# ZYNQ_SOC_ARM.net
KiCad netlist of a schematic drawn in Altium Designer
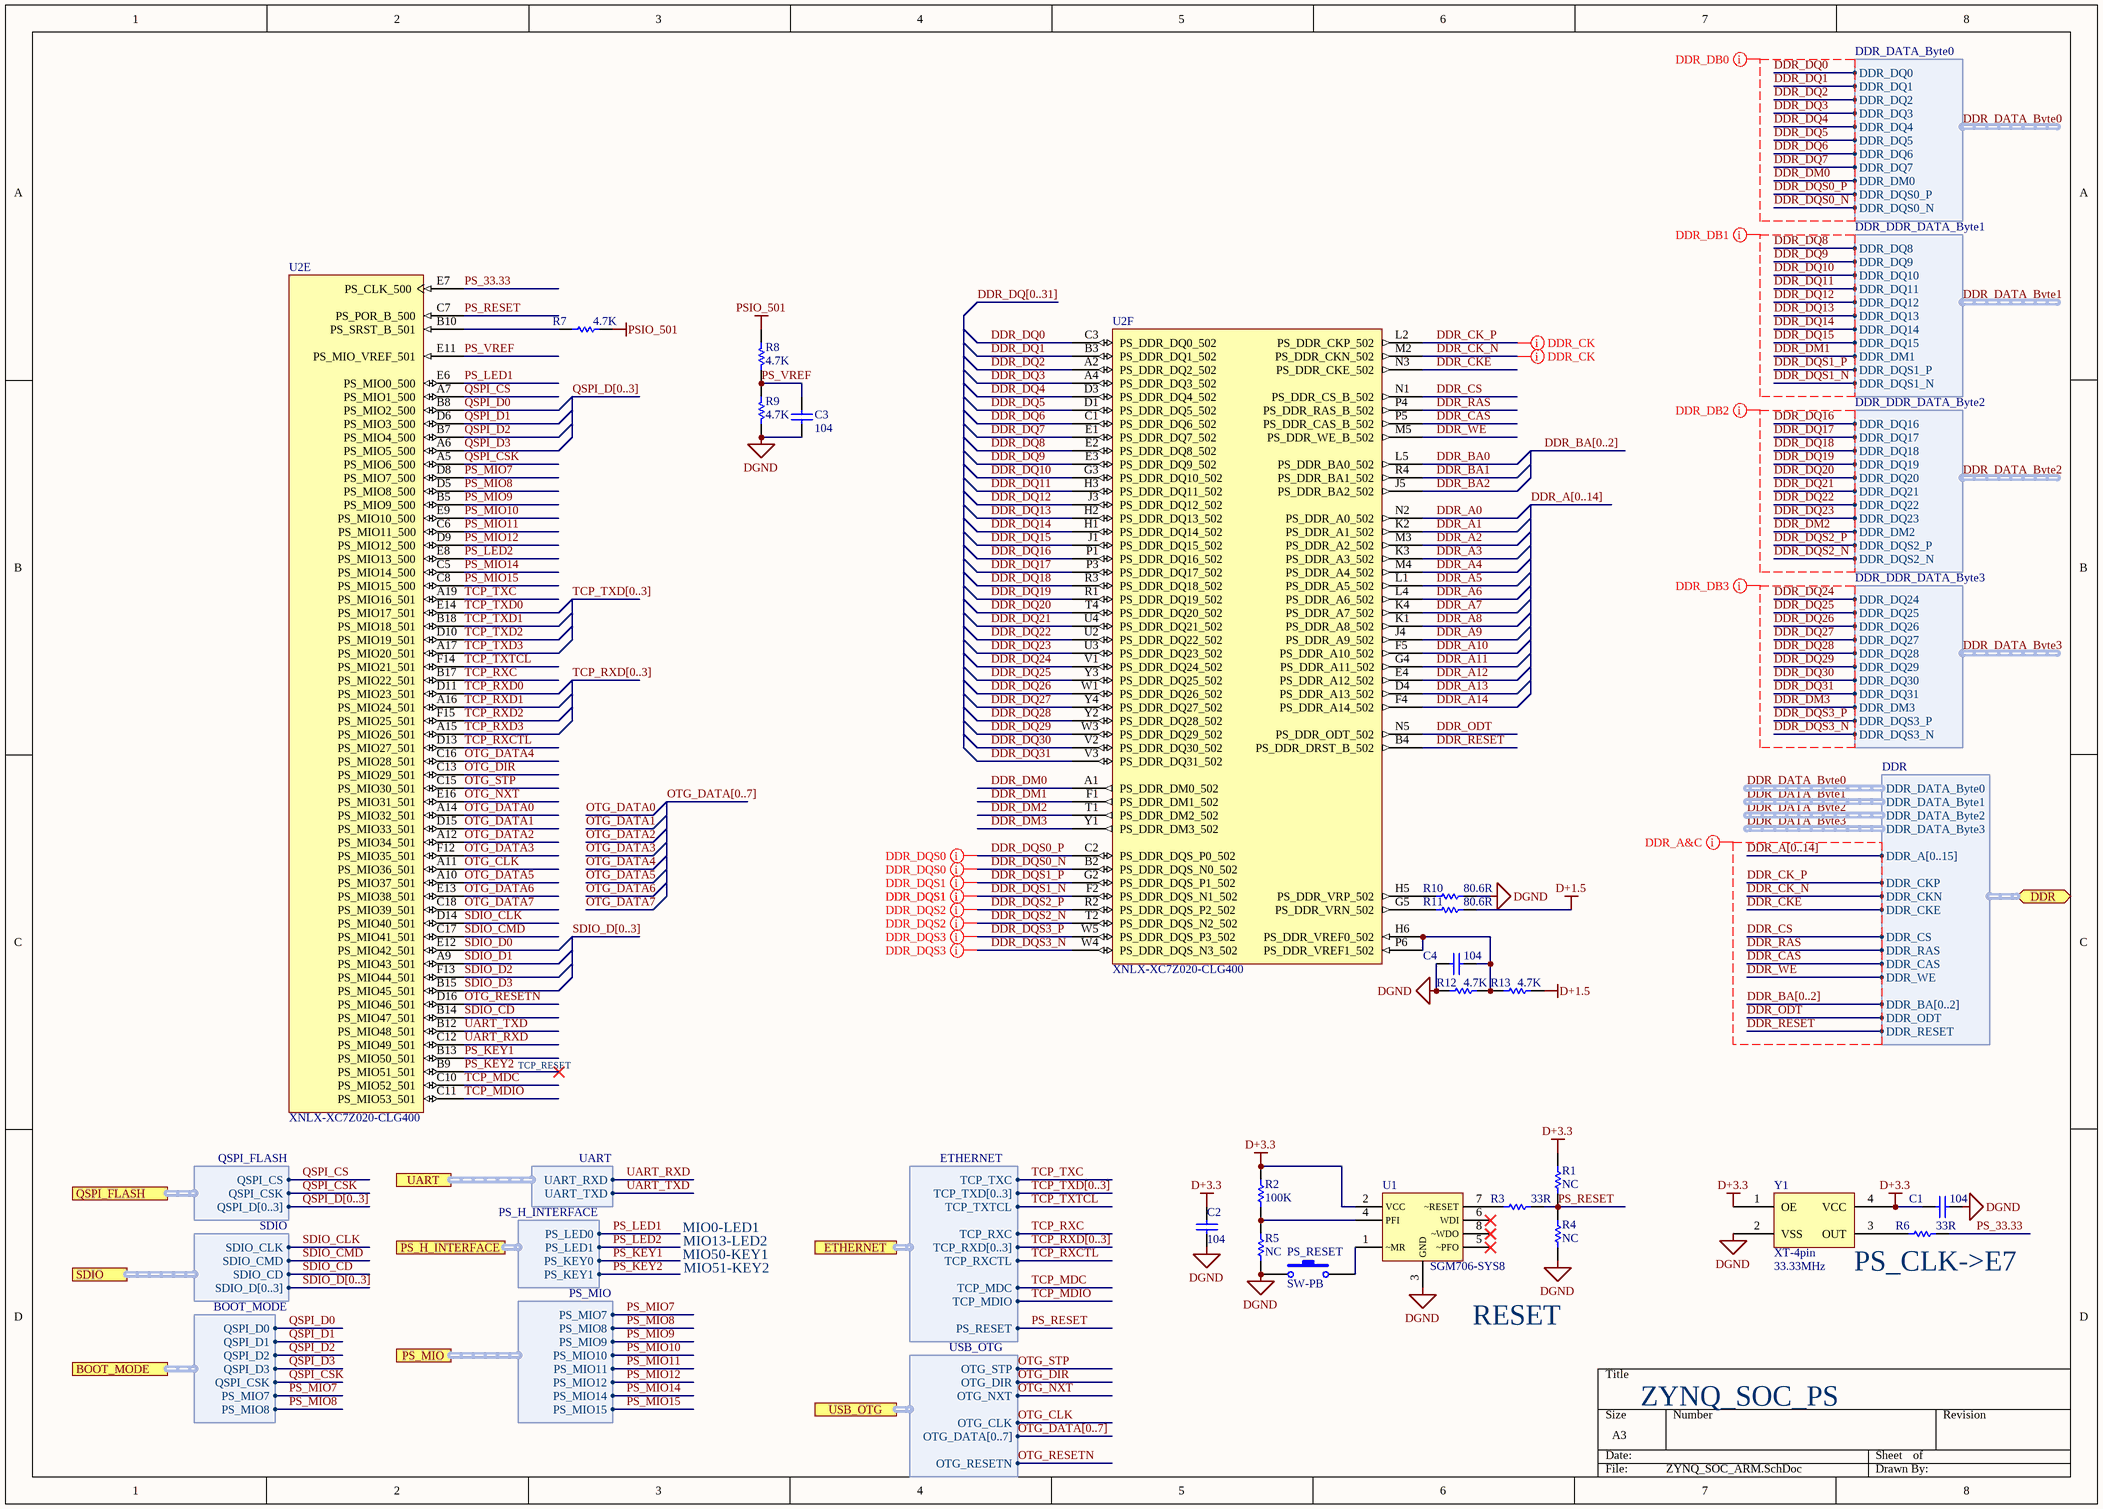
[diagram p0: ZYNQ_SOC_ARM.SchDoc]

(export (version "E")
  (design (tool "Eeschema 10.0.6"))
  (components
    (comp (ref "C1")
      (value "104")
      (footprint "C 0402_LL")
      (description "Capacitor")
      (fields (field (name "PUBLISHER") "Altium Limited"))
      (libsource (lib "Miscellaneous Devices") (part "Cap"))
    )
    (comp (ref "C2")
      (value "104")
      (footprint "C 0402_LL")
      (description "Capacitor")
      (fields (field (name "PUBLISHER") "Altium Limited"))
      (libsource (lib "Miscellaneous Devices") (part "Cap"))
    )
    (comp (ref "C3")
      (value "104")
      (footprint "C 0402_LL")
      (description "Capacitor")
      (fields (field (name "PUBLISHER") "Altium Limited"))
      (libsource (lib "Miscellaneous Devices") (part "Cap"))
    )
    (comp (ref "C4")
      (value "104")
      (footprint "C 0402_LL")
      (description "Capacitor")
      (fields (field (name "PUBLISHER") "Altium Limited"))
      (libsource (lib "Miscellaneous Devices") (part "Cap"))
    )
    (comp (ref "PS_RESET")
      (value "SW-PB")
      (footprint "TSW SMD-3*6*4.3")
      (description "Switch")
      (fields (field (name "PUBLISHER") "Altium Limited"))
      (libsource (lib "Miscellaneous Devices") (part "SW-PB"))
    )
    (comp (ref "R1")
      (value "NC")
      (footprint "R 0402_L")
      (description "Resistor")
      (fields (field (name "PUBLISHER") "Altium Limited"))
      (libsource (lib "Miscellaneous Devices") (part "Res1"))
    )
    (comp (ref "R2")
      (value "100K")
      (footprint "R 0603_L")
      (description "Resistor")
      (fields (field (name "PUBLISHER") "Altium Limited"))
      (libsource (lib "Miscellaneous Devices") (part "Res1"))
    )
    (comp (ref "R3")
      (value "33R")
      (footprint "R 0603_L")
      (description "Resistor")
      (fields (field (name "PUBLISHER") "Altium Limited"))
      (libsource (lib "Miscellaneous Devices") (part "Res1"))
    )
    (comp (ref "R4")
      (value "NC")
      (footprint "R 0402_L")
      (description "Resistor")
      (fields (field (name "PUBLISHER") "Altium Limited"))
      (libsource (lib "Miscellaneous Devices") (part "Res1"))
    )
    (comp (ref "R5")
      (value "NC")
      (footprint "R 0402_L")
      (description "Resistor")
      (fields (field (name "PUBLISHER") "Altium Limited"))
      (libsource (lib "Miscellaneous Devices") (part "Res1"))
    )
    (comp (ref "R6")
      (value "33R")
      (footprint "R 0603_L")
      (description "Resistor")
      (fields (field (name "PUBLISHER") "Altium Limited"))
      (libsource (lib "Miscellaneous Devices") (part "Res1"))
    )
    (comp (ref "R7")
      (value "4.7K")
      (footprint "R 0402_L")
      (description "Resistor")
      (fields (field (name "PUBLISHER") "Altium Limited"))
      (libsource (lib "Miscellaneous Devices") (part "Res1"))
    )
    (comp (ref "R8")
      (value "4.7K")
      (footprint "R 0402_L")
      (description "Resistor")
      (fields (field (name "PUBLISHER") "Altium Limited"))
      (libsource (lib "Miscellaneous Devices") (part "Res1"))
    )
    (comp (ref "R9")
      (value "4.7K")
      (footprint "R 0402_L")
      (description "Resistor")
      (fields (field (name "PUBLISHER") "Altium Limited"))
      (libsource (lib "Miscellaneous Devices") (part "Res1"))
    )
    (comp (ref "R10")
      (value "80.6R")
      (footprint "R 0402_L")
      (description "Resistor")
      (fields (field (name "PUBLISHER") "Altium Limited"))
      (libsource (lib "Miscellaneous Devices") (part "Res1"))
    )
    (comp (ref "R11")
      (value "80.6R")
      (footprint "R 0402_L")
      (description "Resistor")
      (fields (field (name "PUBLISHER") "Altium Limited"))
      (libsource (lib "Miscellaneous Devices") (part "Res1"))
    )
    (comp (ref "R12")
      (value "4.7K")
      (footprint "R 0402_L")
      (description "Resistor")
      (fields (field (name "PUBLISHER") "Altium Limited"))
      (libsource (lib "Miscellaneous Devices") (part "Res1"))
    )
    (comp (ref "R13")
      (value "4.7K")
      (footprint "R 0402_L")
      (description "Resistor")
      (fields (field (name "PUBLISHER") "Altium Limited"))
      (libsource (lib "Miscellaneous Devices") (part "Res1"))
    )
    (comp (ref "U1")
      (value "SGM706-SYS8")
      (footprint "SOP8_N")
      (description "power supply monitoring circuitry for power on time.")
      (libsource (lib "ZYNQ7010_add") (part "SGM706"))
    )
    (comp (ref "U2")
      (value "XNLX-XC7Z020-CLG400")
      (footprint "BGA400")
      (description "xilinx双核A9处理器与FPGA集成的SoC")
      (fields (field (name "MANUFACTURER") "xilinx"))
      (libsource (lib "龙井V1") (part "XNLX-XC7Z020-CLG400"))
    )
    (comp (ref "Y1")
      (value "XT-4pin")
      (footprint "5032(P)")
      (description "有源晶振")
      (fields (field (name "MANUFACTURER") "NC") (field (name "ALTIUM_VALUE") "33.33MHz"))
      (libsource (lib "龙井V1") (part "XT-4pin"))
    )
  )
  (nets
    (net (code "18") (name "/DDR_A0") (class "Default")
      (node (ref "U2") (pin "N2") (pinfunction "PS_DDR_A0_502_N2") (pintype "output"))
    )
    (net (code "19") (name "/DDR_A1") (class "Default")
      (node (ref "U2") (pin "K2") (pinfunction "PS_DDR_A1_502_K2") (pintype "output"))
    )
    (net (code "20") (name "/DDR_A2") (class "Default")
      (node (ref "U2") (pin "M3") (pinfunction "PS_DDR_A2_502_M3") (pintype "output"))
    )
    (net (code "21") (name "/DDR_A3") (class "Default")
      (node (ref "U2") (pin "K3") (pinfunction "PS_DDR_A3_502_K3") (pintype "output"))
    )
    (net (code "22") (name "/DDR_A4") (class "Default")
      (node (ref "U2") (pin "M4") (pinfunction "PS_DDR_A4_502_M4") (pintype "output"))
    )
    (net (code "23") (name "/DDR_A5") (class "Default")
      (node (ref "U2") (pin "L1") (pinfunction "PS_DDR_A5_502_L1") (pintype "output"))
    )
    (net (code "24") (name "/DDR_A6") (class "Default")
      (node (ref "U2") (pin "L4") (pinfunction "PS_DDR_A6_502_L4") (pintype "output"))
    )
    (net (code "25") (name "/DDR_A7") (class "Default")
      (node (ref "U2") (pin "K4") (pinfunction "PS_DDR_A7_502_K4") (pintype "output"))
    )
    (net (code "26") (name "/DDR_A8") (class "Default")
      (node (ref "U2") (pin "K1") (pinfunction "PS_DDR_A8_502_K1") (pintype "output"))
    )
    (net (code "27") (name "/DDR_A9") (class "Default")
      (node (ref "U2") (pin "J4") (pinfunction "PS_DDR_A9_502_J4") (pintype "output"))
    )
    (net (code "28") (name "/DDR_A10") (class "Default")
      (node (ref "U2") (pin "F5") (pinfunction "PS_DDR_A10_502_F5") (pintype "output"))
    )
    (net (code "29") (name "/DDR_A11") (class "Default")
      (node (ref "U2") (pin "G4") (pinfunction "PS_DDR_A11_502_G4") (pintype "output"))
    )
    (net (code "30") (name "/DDR_A12") (class "Default")
      (node (ref "U2") (pin "E4") (pinfunction "PS_DDR_A12_502_E4") (pintype "output"))
    )
    (net (code "31") (name "/DDR_A13") (class "Default")
      (node (ref "U2") (pin "D4") (pinfunction "PS_DDR_A13_502_D4") (pintype "output"))
    )
    (net (code "32") (name "/DDR_A14") (class "Default")
      (node (ref "U2") (pin "F4") (pinfunction "PS_DDR_A14_502_F4") (pintype "output"))
    )
    (net (code "34") (name "/DDR_BA0") (class "Default")
      (node (ref "U2") (pin "L5") (pinfunction "PS_DDR_BA0_502_L5") (pintype "output"))
    )
    (net (code "35") (name "/DDR_BA1") (class "Default")
      (node (ref "U2") (pin "R4") (pinfunction "PS_DDR_BA1_502_R4") (pintype "output"))
    )
    (net (code "36") (name "/DDR_BA2") (class "Default")
      (node (ref "U2") (pin "J5") (pinfunction "PS_DDR_BA2_502_J5") (pintype "output"))
    )
    (net (code "38") (name "/DDR_CAS") (class "Default")
      (node (ref "U2") (pin "P5") (pinfunction "PS_DDR_CAS_B_502_P5") (pintype "output"))
    )
    (net (code "39") (name "/DDR_CKE") (class "Default")
      (node (ref "U2") (pin "N3") (pinfunction "PS_DDR_CKE_502_N3") (pintype "output"))
    )
    (net (code "40") (name "/DDR_CK_N") (class "Default")
      (node (ref "U2") (pin "M2") (pinfunction "PS_DDR_CKN_502_M2") (pintype "output"))
    )
    (net (code "41") (name "/DDR_CK_P") (class "Default")
      (node (ref "U2") (pin "L2") (pinfunction "PS_DDR_CKP_502_L2") (pintype "output"))
    )
    (net (code "42") (name "/DDR_CS") (class "Default")
      (node (ref "U2") (pin "N1") (pinfunction "PS_DDR_CS_B_502_N1") (pintype "output"))
    )
    (net (code "47") (name "/DDR_DM0") (class "Default")
      (node (ref "U2") (pin "A1") (pinfunction "PS_DDR_DM0_502_A1") (pintype "output"))
    )
    (net (code "48") (name "/DDR_DM1") (class "Default")
      (node (ref "U2") (pin "F1") (pinfunction "PS_DDR_DM1_502_F1") (pintype "output"))
    )
    (net (code "49") (name "/DDR_DM2") (class "Default")
      (node (ref "U2") (pin "T1") (pinfunction "PS_DDR_DM2_502_T1") (pintype "output"))
    )
    (net (code "50") (name "/DDR_DM3") (class "Default")
      (node (ref "U2") (pin "Y1") (pinfunction "PS_DDR_DM3_502_Y1") (pintype "output"))
    )
    (net (code "51") (name "/DDR_DQ0") (class "Default")
      (node (ref "U2") (pin "C3") (pinfunction "PS_DDR_DQ0_502_C3") (pintype "bidirectional"))
    )
    (net (code "52") (name "/DDR_DQ1") (class "Default")
      (node (ref "U2") (pin "B3") (pinfunction "PS_DDR_DQ1_502_B3") (pintype "bidirectional"))
    )
    (net (code "53") (name "/DDR_DQ2") (class "Default")
      (node (ref "U2") (pin "A2") (pinfunction "PS_DDR_DQ2_502_A2") (pintype "bidirectional"))
    )
    (net (code "54") (name "/DDR_DQ3") (class "Default")
      (node (ref "U2") (pin "A4") (pinfunction "PS_DDR_DQ3_502_A4") (pintype "bidirectional"))
    )
    (net (code "55") (name "/DDR_DQ4") (class "Default")
      (node (ref "U2") (pin "D3") (pinfunction "PS_DDR_DQ4_502_D3") (pintype "bidirectional"))
    )
    (net (code "56") (name "/DDR_DQ5") (class "Default")
      (node (ref "U2") (pin "D1") (pinfunction "PS_DDR_DQ5_502_D1") (pintype "bidirectional"))
    )
    (net (code "57") (name "/DDR_DQ6") (class "Default")
      (node (ref "U2") (pin "C1") (pinfunction "PS_DDR_DQ6_502_C1") (pintype "bidirectional"))
    )
    (net (code "58") (name "/DDR_DQ7") (class "Default")
      (node (ref "U2") (pin "E1") (pinfunction "PS_DDR_DQ7_502_E1") (pintype "bidirectional"))
    )
    (net (code "59") (name "/DDR_DQ8") (class "Default")
      (node (ref "U2") (pin "E2") (pinfunction "PS_DDR_DQ8_502_E2") (pintype "bidirectional"))
    )
    (net (code "60") (name "/DDR_DQ9") (class "Default")
      (node (ref "U2") (pin "E3") (pinfunction "PS_DDR_DQ9_502_E3") (pintype "bidirectional"))
    )
    (net (code "61") (name "/DDR_DQ10") (class "Default")
      (node (ref "U2") (pin "G3") (pinfunction "PS_DDR_DQ10_502_G3") (pintype "bidirectional"))
    )
    (net (code "62") (name "/DDR_DQ11") (class "Default")
      (node (ref "U2") (pin "H3") (pinfunction "PS_DDR_DQ11_502_H3") (pintype "bidirectional"))
    )
    (net (code "63") (name "/DDR_DQ12") (class "Default")
      (node (ref "U2") (pin "J3") (pinfunction "PS_DDR_DQ12_502_J3") (pintype "bidirectional"))
    )
    (net (code "64") (name "/DDR_DQ13") (class "Default")
      (node (ref "U2") (pin "H2") (pinfunction "PS_DDR_DQ13_502_H2") (pintype "bidirectional"))
    )
    (net (code "65") (name "/DDR_DQ14") (class "Default")
      (node (ref "U2") (pin "H1") (pinfunction "PS_DDR_DQ14_502_H1") (pintype "bidirectional"))
    )
    (net (code "66") (name "/DDR_DQ15") (class "Default")
      (node (ref "U2") (pin "J1") (pinfunction "PS_DDR_DQ15_502_J1") (pintype "bidirectional"))
    )
    (net (code "67") (name "/DDR_DQ16") (class "Default")
      (node (ref "U2") (pin "P1") (pinfunction "PS_DDR_DQ16_502_P1") (pintype "bidirectional"))
    )
    (net (code "68") (name "/DDR_DQ17") (class "Default")
      (node (ref "U2") (pin "P3") (pinfunction "PS_DDR_DQ17_502_P3") (pintype "bidirectional"))
    )
    (net (code "69") (name "/DDR_DQ18") (class "Default")
      (node (ref "U2") (pin "R3") (pinfunction "PS_DDR_DQ18_502_R3") (pintype "bidirectional"))
    )
    (net (code "70") (name "/DDR_DQ19") (class "Default")
      (node (ref "U2") (pin "R1") (pinfunction "PS_DDR_DQ19_502_R1") (pintype "bidirectional"))
    )
    (net (code "71") (name "/DDR_DQ20") (class "Default")
      (node (ref "U2") (pin "T4") (pinfunction "PS_DDR_DQ20_502_T4") (pintype "bidirectional"))
    )
    (net (code "72") (name "/DDR_DQ21") (class "Default")
      (node (ref "U2") (pin "U4") (pinfunction "PS_DDR_DQ21_502_U4") (pintype "bidirectional"))
    )
    (net (code "73") (name "/DDR_DQ22") (class "Default")
      (node (ref "U2") (pin "U2") (pinfunction "PS_DDR_DQ22_502_U2") (pintype "bidirectional"))
    )
    (net (code "74") (name "/DDR_DQ23") (class "Default")
      (node (ref "U2") (pin "U3") (pinfunction "PS_DDR_DQ23_502_U3") (pintype "bidirectional"))
    )
    (net (code "75") (name "/DDR_DQ24") (class "Default")
      (node (ref "U2") (pin "V1") (pinfunction "PS_DDR_DQ24_502_V1") (pintype "bidirectional"))
    )
    (net (code "76") (name "/DDR_DQ25") (class "Default")
      (node (ref "U2") (pin "Y3") (pinfunction "PS_DDR_DQ25_502_Y3") (pintype "bidirectional"))
    )
    (net (code "77") (name "/DDR_DQ26") (class "Default")
      (node (ref "U2") (pin "W1") (pinfunction "PS_DDR_DQ26_502_W1") (pintype "bidirectional"))
    )
    (net (code "78") (name "/DDR_DQ27") (class "Default")
      (node (ref "U2") (pin "Y4") (pinfunction "PS_DDR_DQ27_502_Y4") (pintype "bidirectional"))
    )
    (net (code "79") (name "/DDR_DQ28") (class "Default")
      (node (ref "U2") (pin "Y2") (pinfunction "PS_DDR_DQ28_502_Y2") (pintype "bidirectional"))
    )
    (net (code "80") (name "/DDR_DQ29") (class "Default")
      (node (ref "U2") (pin "W3") (pinfunction "PS_DDR_DQ29_502_W3") (pintype "bidirectional"))
    )
    (net (code "81") (name "/DDR_DQ30") (class "Default")
      (node (ref "U2") (pin "V2") (pinfunction "PS_DDR_DQ30_502_V2") (pintype "bidirectional"))
    )
    (net (code "82") (name "/DDR_DQ31") (class "Default")
      (node (ref "U2") (pin "V3") (pinfunction "PS_DDR_DQ31_502_V3") (pintype "bidirectional"))
    )
    (net (code "83") (name "/DDR_DQS0_N") (class "Default")
      (node (ref "U2") (pin "B2") (pinfunction "PS_DDR_DQS_N0_502_B2") (pintype "bidirectional"))
    )
    (net (code "84") (name "/DDR_DQS0_P") (class "Default")
      (node (ref "U2") (pin "C2") (pinfunction "PS_DDR_DQS_P0_502_C2") (pintype "bidirectional"))
    )
    (net (code "85") (name "/DDR_DQS1_N") (class "Default")
      (node (ref "U2") (pin "F2") (pinfunction "PS_DDR_DQS_N1_502_F2") (pintype "bidirectional"))
    )
    (net (code "86") (name "/DDR_DQS1_P") (class "Default")
      (node (ref "U2") (pin "G2") (pinfunction "PS_DDR_DQS_P1_502_G2") (pintype "bidirectional"))
    )
    (net (code "87") (name "/DDR_DQS2_N") (class "Default")
      (node (ref "U2") (pin "T2") (pinfunction "PS_DDR_DQS_N2_502_T2") (pintype "bidirectional"))
    )
    (net (code "88") (name "/DDR_DQS2_P") (class "Default")
      (node (ref "U2") (pin "R2") (pinfunction "PS_DDR_DQS_P2_502_R2") (pintype "bidirectional"))
    )
    (net (code "89") (name "/DDR_DQS3_N") (class "Default")
      (node (ref "U2") (pin "W4") (pinfunction "PS_DDR_DQS_N3_502_W4") (pintype "bidirectional"))
    )
    (net (code "90") (name "/DDR_DQS3_P") (class "Default")
      (node (ref "U2") (pin "W5") (pinfunction "PS_DDR_DQS_P3_502_W5") (pintype "bidirectional"))
    )
    (net (code "92") (name "/DDR_ODT") (class "Default")
      (node (ref "U2") (pin "N5") (pinfunction "PS_DDR_ODT_502_N5") (pintype "output"))
    )
    (net (code "93") (name "/DDR_RAS") (class "Default")
      (node (ref "U2") (pin "P4") (pinfunction "PS_DDR_RAS_B_502_P4") (pintype "output"))
    )
    (net (code "94") (name "/DDR_RESET") (class "Default")
      (node (ref "U2") (pin "B4") (pinfunction "PS_DDR_DRST_B_502_B4") (pintype "output"))
    )
    (net (code "95") (name "/DDR_WE") (class "Default")
      (node (ref "U2") (pin "M5") (pinfunction "PS_DDR_WE_B_502_M5") (pintype "output"))
    )
    (net (code "97") (name "/OTG_CLK") (class "Default")
      (node (ref "U2") (pin "A11") (pinfunction "PS_MIO36_501_A11") (pintype "bidirectional"))
    )
    (net (code "98") (name "/OTG_DATA0") (class "Default")
      (node (ref "U2") (pin "A14") (pinfunction "PS_MIO32_501_A14") (pintype "bidirectional"))
    )
    (net (code "99") (name "/OTG_DATA1") (class "Default")
      (node (ref "U2") (pin "D15") (pinfunction "PS_MIO33_501_D15") (pintype "bidirectional"))
    )
    (net (code "100") (name "/OTG_DATA2") (class "Default")
      (node (ref "U2") (pin "A12") (pinfunction "PS_MIO34_501_A12") (pintype "bidirectional"))
    )
    (net (code "101") (name "/OTG_DATA3") (class "Default")
      (node (ref "U2") (pin "F12") (pinfunction "PS_MIO35_501_F12") (pintype "bidirectional"))
    )
    (net (code "102") (name "/OTG_DATA4") (class "Default")
      (node (ref "U2") (pin "C16") (pinfunction "PS_MIO28_501_C16") (pintype "bidirectional"))
    )
    (net (code "103") (name "/OTG_DATA5") (class "Default")
      (node (ref "U2") (pin "A10") (pinfunction "PS_MIO37_501_A10") (pintype "bidirectional"))
    )
    (net (code "104") (name "/OTG_DATA6") (class "Default")
      (node (ref "U2") (pin "E13") (pinfunction "PS_MIO38_501_E13") (pintype "bidirectional"))
    )
    (net (code "105") (name "/OTG_DATA7") (class "Default")
      (node (ref "U2") (pin "C18") (pinfunction "PS_MIO39_501_C18") (pintype "bidirectional"))
    )
    (net (code "107") (name "/OTG_DIR") (class "Default")
      (node (ref "U2") (pin "C13") (pinfunction "PS_MIO29_501_C13") (pintype "bidirectional"))
    )
    (net (code "108") (name "/OTG_NXT") (class "Default")
      (node (ref "U2") (pin "E16") (pinfunction "PS_MIO31_501_E16") (pintype "bidirectional"))
    )
    (net (code "109") (name "/OTG_RESETN") (class "Default")
      (node (ref "U2") (pin "D16") (pinfunction "PS_MIO46_501_D16") (pintype "bidirectional"))
    )
    (net (code "110") (name "/OTG_STP") (class "Default")
      (node (ref "U2") (pin "C15") (pinfunction "PS_MIO30_501_C15") (pintype "bidirectional"))
    )
    (net (code "111") (name "/PS_33.33") (class "Default")
      (node (ref "R6") (pin "2") (pinfunction "2_2") (pintype "passive"))
      (node (ref "U2") (pin "E7") (pinfunction "PS_CLK_500_E7") (pintype "input"))
    )
    (net (code "112") (name "/PS_KEY1") (class "Default")
      (node (ref "U2") (pin "B13") (pinfunction "PS_MIO50_501_B13") (pintype "bidirectional"))
    )
    (net (code "113") (name "/PS_KEY2") (class "Default")
      (node (ref "U2") (pin "B9") (pinfunction "PS_MIO51_501_B9") (pintype "bidirectional+no_connect"))
    )
    (net (code "114") (name "/PS_LED1") (class "Default")
      (node (ref "U2") (pin "E6") (pinfunction "PS_MIO0_500_E6") (pintype "bidirectional"))
    )
    (net (code "115") (name "/PS_LED2") (class "Default")
      (node (ref "U2") (pin "E8") (pinfunction "PS_MIO13_500_E8") (pintype "bidirectional"))
    )
    (net (code "116") (name "/PS_MIO7") (class "Default")
      (node (ref "U2") (pin "D8") (pinfunction "PS_MIO7_500_D8") (pintype "bidirectional"))
    )
    (net (code "117") (name "/PS_MIO8") (class "Default")
      (node (ref "U2") (pin "D5") (pinfunction "PS_MIO8_500_D5") (pintype "bidirectional"))
    )
    (net (code "118") (name "/PS_MIO9") (class "Default")
      (node (ref "U2") (pin "B5") (pinfunction "PS_MIO9_500_B5") (pintype "bidirectional"))
    )
    (net (code "119") (name "/PS_MIO10") (class "Default")
      (node (ref "U2") (pin "E9") (pinfunction "PS_MIO10_500_E9") (pintype "bidirectional"))
    )
    (net (code "120") (name "/PS_MIO11") (class "Default")
      (node (ref "U2") (pin "C6") (pinfunction "PS_MIO11_500_C6") (pintype "bidirectional"))
    )
    (net (code "121") (name "/PS_MIO12") (class "Default")
      (node (ref "U2") (pin "D9") (pinfunction "PS_MIO12_500_D9") (pintype "bidirectional"))
    )
    (net (code "122") (name "/PS_MIO14") (class "Default")
      (node (ref "U2") (pin "C5") (pinfunction "PS_MIO14_500_C5") (pintype "bidirectional"))
    )
    (net (code "123") (name "/PS_MIO15") (class "Default")
      (node (ref "U2") (pin "C8") (pinfunction "PS_MIO15_500_C8") (pintype "bidirectional"))
    )
    (net (code "124") (name "/PS_RESET") (class "Default")
      (node (ref "R1") (pin "1") (pinfunction "1_1") (pintype "passive"))
      (node (ref "R3") (pin "2") (pinfunction "2_2") (pintype "passive"))
      (node (ref "R4") (pin "2") (pinfunction "2_2") (pintype "passive"))
      (node (ref "U2") (pin "C7") (pinfunction "PS_POR_B_500_C7") (pintype "input"))
    )
    (net (code "125") (name "/PS_VREF") (class "Default")
      (node (ref "C3") (pin "2") (pinfunction "2_2") (pintype "passive"))
      (node (ref "R8") (pin "1") (pinfunction "1_1") (pintype "passive"))
      (node (ref "R9") (pin "2") (pinfunction "2_2") (pintype "passive"))
      (node (ref "U2") (pin "E11") (pinfunction "PS_MIO_VREF_501_E11") (pintype "input"))
    )
    (net (code "126") (name "/QSPI_CS") (class "Default")
      (node (ref "U2") (pin "A7") (pinfunction "PS_MIO1_500_A7") (pintype "bidirectional"))
    )
    (net (code "127") (name "/QSPI_CSK") (class "Default")
      (node (ref "U2") (pin "A5") (pinfunction "PS_MIO6_500_A5") (pintype "bidirectional"))
    )
    (net (code "128") (name "/QSPI_D0") (class "Default")
      (node (ref "U2") (pin "B8") (pinfunction "PS_MIO2_500_B8") (pintype "bidirectional"))
    )
    (net (code "129") (name "/QSPI_D1") (class "Default")
      (node (ref "U2") (pin "D6") (pinfunction "PS_MIO3_500_D6") (pintype "bidirectional"))
    )
    (net (code "130") (name "/QSPI_D2") (class "Default")
      (node (ref "U2") (pin "B7") (pinfunction "PS_MIO4_500_B7") (pintype "bidirectional"))
    )
    (net (code "131") (name "/QSPI_D3") (class "Default")
      (node (ref "U2") (pin "A6") (pinfunction "PS_MIO5_500_A6") (pintype "bidirectional"))
    )
    (net (code "133") (name "/SDIO_CD") (class "Default")
      (node (ref "U2") (pin "B14") (pinfunction "PS_MIO47_501_B14") (pintype "bidirectional"))
    )
    (net (code "134") (name "/SDIO_CLK") (class "Default")
      (node (ref "U2") (pin "D14") (pinfunction "PS_MIO40_501_D14") (pintype "bidirectional"))
    )
    (net (code "135") (name "/SDIO_CMD") (class "Default")
      (node (ref "U2") (pin "C17") (pinfunction "PS_MIO41_501_C17") (pintype "bidirectional"))
    )
    (net (code "136") (name "/SDIO_D0") (class "Default")
      (node (ref "U2") (pin "E12") (pinfunction "PS_MIO42_501_E12") (pintype "bidirectional"))
    )
    (net (code "137") (name "/SDIO_D1") (class "Default")
      (node (ref "U2") (pin "A9") (pinfunction "PS_MIO43_501_A9") (pintype "bidirectional"))
    )
    (net (code "138") (name "/SDIO_D2") (class "Default")
      (node (ref "U2") (pin "F13") (pinfunction "PS_MIO44_501_F13") (pintype "bidirectional"))
    )
    (net (code "139") (name "/SDIO_D3") (class "Default")
      (node (ref "U2") (pin "B15") (pinfunction "PS_MIO45_501_B15") (pintype "bidirectional"))
    )
    (net (code "142") (name "/TCP_MDC") (class "Default")
      (node (ref "U2") (pin "C10") (pinfunction "PS_MIO52_501_C10") (pintype "bidirectional"))
    )
    (net (code "143") (name "/TCP_MDIO") (class "Default")
      (node (ref "U2") (pin "C11") (pinfunction "PS_MIO53_501_C11") (pintype "bidirectional"))
    )
    (net (code "144") (name "/TCP_RXC") (class "Default")
      (node (ref "U2") (pin "B17") (pinfunction "PS_MIO22_501_B17") (pintype "bidirectional"))
    )
    (net (code "145") (name "/TCP_RXCTL") (class "Default")
      (node (ref "U2") (pin "D13") (pinfunction "PS_MIO27_501_D13") (pintype "bidirectional"))
    )
    (net (code "146") (name "/TCP_RXD0") (class "Default")
      (node (ref "U2") (pin "D11") (pinfunction "PS_MIO23_501_D11") (pintype "bidirectional"))
    )
    (net (code "147") (name "/TCP_RXD1") (class "Default")
      (node (ref "U2") (pin "A16") (pinfunction "PS_MIO24_501_A16") (pintype "bidirectional"))
    )
    (net (code "148") (name "/TCP_RXD2") (class "Default")
      (node (ref "U2") (pin "F15") (pinfunction "PS_MIO25_501_F15") (pintype "bidirectional"))
    )
    (net (code "149") (name "/TCP_RXD3") (class "Default")
      (node (ref "U2") (pin "A15") (pinfunction "PS_MIO26_501_A15") (pintype "bidirectional"))
    )
    (net (code "151") (name "/TCP_TXC") (class "Default")
      (node (ref "U2") (pin "A19") (pinfunction "PS_MIO16_501_A19") (pintype "bidirectional"))
    )
    (net (code "152") (name "/TCP_TXD0") (class "Default")
      (node (ref "U2") (pin "E14") (pinfunction "PS_MIO17_501_E14") (pintype "bidirectional"))
    )
    (net (code "153") (name "/TCP_TXD1") (class "Default")
      (node (ref "U2") (pin "B18") (pinfunction "PS_MIO18_501_B18") (pintype "bidirectional"))
    )
    (net (code "154") (name "/TCP_TXD2") (class "Default")
      (node (ref "U2") (pin "D10") (pinfunction "PS_MIO19_501_D10") (pintype "bidirectional"))
    )
    (net (code "155") (name "/TCP_TXD3") (class "Default")
      (node (ref "U2") (pin "A17") (pinfunction "PS_MIO20_501_A17") (pintype "bidirectional"))
    )
    (net (code "157") (name "/TCP_TXTCL") (class "Default")
      (node (ref "U2") (pin "F14") (pinfunction "PS_MIO21_501_F14") (pintype "bidirectional"))
    )
    (net (code "158") (name "/UART_RXD") (class "Default")
      (node (ref "U2") (pin "C12") (pinfunction "PS_MIO49_501_C12") (pintype "bidirectional"))
    )
    (net (code "159") (name "/UART_TXD") (class "Default")
      (node (ref "U2") (pin "B12") (pinfunction "PS_MIO48_501_B12") (pintype "bidirectional"))
    )
    (net (code "174") (name "D+1.5") (class "Default")
      (node (ref "R11") (pin "2") (pinfunction "2_2") (pintype "passive"))
      (node (ref "R13") (pin "2") (pinfunction "2_2") (pintype "passive"))
    )
    (net (code "175") (name "D+3.3") (class "Default")
      (node (ref "C1") (pin "1") (pinfunction "1_1") (pintype "passive"))
      (node (ref "C2") (pin "1") (pinfunction "1_1") (pintype "passive"))
      (node (ref "R1") (pin "2") (pinfunction "2_2") (pintype "passive"))
      (node (ref "R2") (pin "2") (pinfunction "2_2") (pintype "passive"))
      (node (ref "U1") (pin "2") (pinfunction "VCC_2") (pintype "passive"))
      (node (ref "Y1") (pin "1") (pinfunction "OE_1") (pintype "passive"))
      (node (ref "Y1") (pin "4") (pinfunction "VCC_4") (pintype "passive"))
    )
    (net (code "176") (name "DGND") (class "Default")
      (node (ref "C1") (pin "2") (pinfunction "2_2") (pintype "passive"))
      (node (ref "C2") (pin "2") (pinfunction "2_2") (pintype "passive"))
      (node (ref "C3") (pin "1") (pinfunction "1_1") (pintype "passive"))
      (node (ref "C4") (pin "1") (pinfunction "1_1") (pintype "passive"))
      (node (ref "PS_RESET") (pin "1") (pinfunction "1_1") (pintype "passive"))
      (node (ref "R10") (pin "2") (pinfunction "2_2") (pintype "passive"))
      (node (ref "R12") (pin "1") (pinfunction "1_1") (pintype "passive"))
      (node (ref "R4") (pin "1") (pinfunction "1_1") (pintype "passive"))
      (node (ref "R5") (pin "1") (pinfunction "1_1") (pintype "passive"))
      (node (ref "R9") (pin "1") (pinfunction "1_1") (pintype "passive"))
      (node (ref "U1") (pin "3") (pinfunction "GND_3") (pintype "passive"))
      (node (ref "Y1") (pin "2") (pinfunction "VSS_2") (pintype "passive"))
    )
    (net (code "177") (name "Net-(U1-PFI)") (class "Default")
      (node (ref "R2") (pin "1") (pinfunction "1_1") (pintype "passive"))
      (node (ref "R5") (pin "2") (pinfunction "2_2") (pintype "passive"))
      (node (ref "U1") (pin "4") (pinfunction "PFI_4") (pintype "passive"))
    )
    (net (code "178") (name "Net-(U1-~MR)") (class "Default")
      (node (ref "PS_RESET") (pin "2") (pinfunction "2_2") (pintype "passive"))
      (node (ref "U1") (pin "1") (pinfunction "~MR_1") (pintype "passive"))
    )
    (net (code "179") (name "Net-(U1-~RESET)") (class "Default")
      (node (ref "R3") (pin "1") (pinfunction "1_1") (pintype "passive"))
      (node (ref "U1") (pin "7") (pinfunction "~RESET_7") (pintype "passive"))
    )
    (net (code "180") (name "Net-(U2E-PS_SRST_B_501)") (class "Default")
      (node (ref "R7") (pin "1") (pinfunction "1_1") (pintype "passive"))
      (node (ref "U2") (pin "B10") (pinfunction "PS_SRST_B_501_B10") (pintype "input"))
    )
    (net (code "181") (name "Net-(U2F-PS_DDR_VREF0_502)") (class "Default")
      (node (ref "C4") (pin "2") (pinfunction "2_2") (pintype "passive"))
      (node (ref "R12") (pin "2") (pinfunction "2_2") (pintype "passive"))
      (node (ref "R13") (pin "1") (pinfunction "1_1") (pintype "passive"))
      (node (ref "U2") (pin "H6") (pinfunction "PS_DDR_VREF0_502_H6") (pintype "input"))
      (node (ref "U2") (pin "P6") (pinfunction "PS_DDR_VREF1_502_P6") (pintype "input"))
    )
    (net (code "182") (name "Net-(U2F-PS_DDR_VRN_502)") (class "Default")
      (node (ref "R11") (pin "1") (pinfunction "1_1") (pintype "passive"))
      (node (ref "U2") (pin "G5") (pinfunction "PS_DDR_VRN_502_G5") (pintype "output"))
    )
    (net (code "183") (name "Net-(U2F-PS_DDR_VRP_502)") (class "Default")
      (node (ref "R10") (pin "1") (pinfunction "1_1") (pintype "passive"))
      (node (ref "U2") (pin "H5") (pinfunction "PS_DDR_VRP_502_H5") (pintype "output"))
    )
    (net (code "184") (name "Net-(Y1-OUT)") (class "Default")
      (node (ref "R6") (pin "1") (pinfunction "1_1") (pintype "passive"))
      (node (ref "Y1") (pin "3") (pinfunction "OUT_3") (pintype "passive"))
    )
    (net (code "185") (name "PSIO_501") (class "Default")
      (node (ref "R7") (pin "2") (pinfunction "2_2") (pintype "passive"))
      (node (ref "R8") (pin "2") (pinfunction "2_2") (pintype "passive"))
    )
    (net (code "186") (name "unconnected-(U1-WDI-Pad6)") (class "Default")
      (node (ref "U1") (pin "6") (pinfunction "WDI_6") (pintype "passive+no_connect"))
    )
    (net (code "187") (name "unconnected-(U1-~PFO-Pad5)") (class "Default")
      (node (ref "U1") (pin "5") (pinfunction "~PFO_5") (pintype "passive+no_connect"))
    )
    (net (code "188") (name "unconnected-(U1-~WDO-Pad8)") (class "Default")
      (node (ref "U1") (pin "8") (pinfunction "~WDO_8") (pintype "passive+no_connect"))
    )
  )
)
